# switch.net
KiCad netlist of a schematic drawn in EAGLE
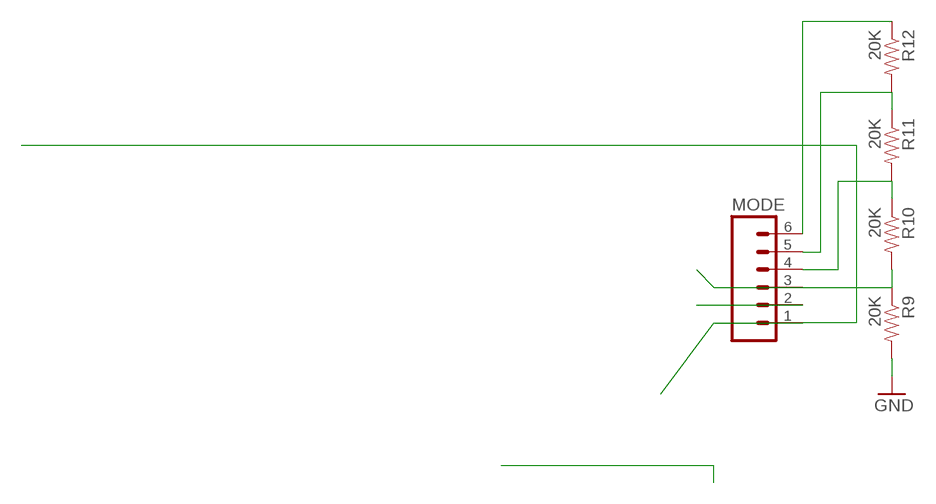
[diagram p0: schematic, sheet 1]

(export (version "E")
  (design (tool "Eeschema 10.0.6"))
  (components
    (comp (ref "MODE")
      (value "M06SILK_FEMALE_PTH")
      (footprint "eagle-import:1X06")
      (libsource (lib "eagle-import") (part "M06SILK_FEMALE_PTH"))
    )
    (comp (ref "R9")
      (value "20K")
      (footprint "eagle-import:AXIAL-0.3")
      (libsource (lib "eagle-import") (part "RESISTORAXIAL-0.3"))
    )
    (comp (ref "R10")
      (value "20K")
      (footprint "eagle-import:AXIAL-0.3")
      (libsource (lib "eagle-import") (part "RESISTORAXIAL-0.3"))
    )
    (comp (ref "R11")
      (value "20K")
      (footprint "eagle-import:AXIAL-0.3")
      (libsource (lib "eagle-import") (part "RESISTORAXIAL-0.3"))
    )
    (comp (ref "R12")
      (value "20K")
      (footprint "eagle-import:AXIAL-0.3")
      (libsource (lib "eagle-import") (part "RESISTORAXIAL-0.3"))
    )
  )
  (nets
    (net (code "1") (name "GND") (class "Default")
      (node (ref "MODE") (pin "2") (pinfunction "2_2") (pintype "passive"))
      (node (ref "R9") (pin "P$2") (pinfunction "2_P$2") (pintype "passive"))
    )
    (net (code "2") (name "Net-(R10-1)") (class "Default")
      (node (ref "MODE") (pin "4") (pinfunction "4_4") (pintype "passive"))
      (node (ref "R10") (pin "P$1") (pinfunction "1_P$1") (pintype "passive"))
      (node (ref "R11") (pin "P$2") (pinfunction "2_P$2") (pintype "passive"))
    )
    (net (code "3") (name "Net-(R10-2)") (class "Default")
      (node (ref "MODE") (pin "3") (pinfunction "3_3") (pintype "passive"))
      (node (ref "R10") (pin "P$2") (pinfunction "2_P$2") (pintype "passive"))
      (node (ref "R9") (pin "P$1") (pinfunction "1_P$1") (pintype "passive"))
    )
    (net (code "4") (name "Net-(R11-1)") (class "Default")
      (node (ref "MODE") (pin "5") (pinfunction "5_5") (pintype "passive"))
      (node (ref "R11") (pin "P$1") (pinfunction "1_P$1") (pintype "passive"))
      (node (ref "R12") (pin "P$2") (pinfunction "2_P$2") (pintype "passive"))
    )
    (net (code "5") (name "Net-(R12-1)") (class "Default")
      (node (ref "MODE") (pin "6") (pinfunction "6_6") (pintype "passive"))
      (node (ref "R12") (pin "P$1") (pinfunction "1_P$1") (pintype "passive"))
    )
    (net (code "6") (name "unconnected-(MODE-Pad1)") (class "Default")
      (node (ref "MODE") (pin "1") (pinfunction "1_1") (pintype "passive"))
    )
  )
)
